# fram_rtc.net
KiCad netlist of a schematic drawn in Altium Designer
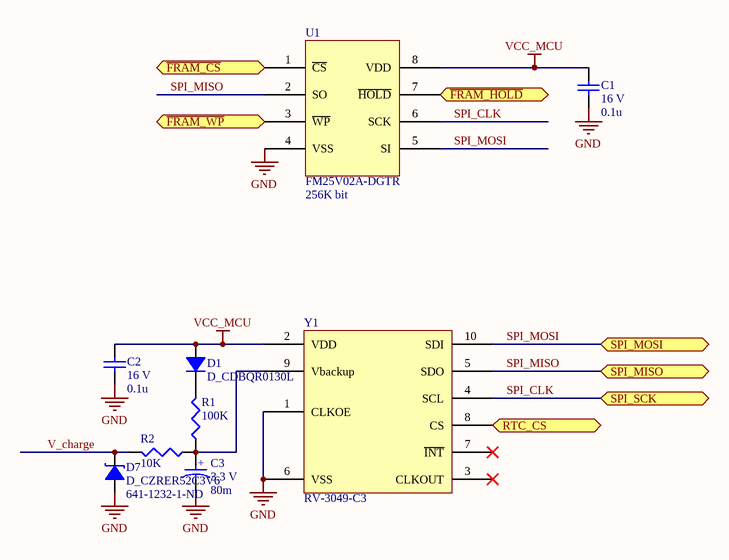
[diagram p0: fram_rtc.SchDoc]

(export (version "E")
  (design (tool "Eeschema 10.0.6"))
  (components
    (comp (ref "C1")
      (value "0.1u")
      (footprint "0402")
      (description "Ceramic capacitor, 0.1u, 16 V, 0402 package")
      (fields
        (field (name "VOLTAGE RATED") "16 V")
        (field (name "TOLERANCE") "10%")
        (field (name "Comment") "Ceramic capacitor")
      )
      (libsource (lib "rlc") (part "C_0.1u_16V_0402_ceramic"))
    )
    (comp (ref "C2")
      (value "0.1u")
      (footprint "0402")
      (description "Ceramic capacitor, 0.1u, 16 V, 0402 package")
      (fields
        (field (name "VOLTAGE RATED") "16 V")
        (field (name "TOLERANCE") "10%")
        (field (name "Comment") "Ceramic capacitor")
      )
      (libsource (lib "rlc") (part "C_0.1u_16V_0402_ceramic"))
    )
    (comp (ref "C3")
      (value "80m")
      (footprint "XH414HG-IV01E")
      (description "Electric double Layer Capacitors")
      (fields
        (field (name "VOLTAGE RATED") "3.3 V")
        (field (name "Comment") "Electric Double Layer Capacitors")
      )
      (libsource (lib "rlc") (part "C_80m_3.3V_supercap"))
    )
    (comp (ref "D1")
      (value "D_CDBQR0130L")
      (footprint "0402 - DIODE")
      (description "SMD Schottky Barrier Diode")
      (libsource (lib "rlc") (part "D_CDBQR0130L"))
    )
    (comp (ref "D7")
      (value "D_CZRER52C3V6")
      (footprint "0503/SOD-723F")
      (description "SURFACE MOUNT ZENER DIODE")
      (fields (field (name "SUPPLIER PART NUMBER 1") "641-1232-1-ND"))
      (libsource (lib "rlc") (part "D_CZRER52C3V6"))
    )
    (comp (ref "R1")
      (value "100K")
      (footprint "0402")
      (description "Chip resistor, 100K, 0402 package")
      (fields (field (name "TOLERANCE") "1%") (field (name "POWER") "1/16 W"))
      (libsource (lib "rlc") (part "R_100K_0402"))
    )
    (comp (ref "R2")
      (value "10K")
      (footprint "0402")
      (description "Chip resistor, 10K, 0402 package")
      (fields (field (name "TOLERANCE") "1%") (field (name "POWER") "1/16 W"))
      (libsource (lib "rlc") (part "R_10K_0402"))
    )
    (comp (ref "U1")
      (value "FM25V02A-DGTR")
      (footprint "TDFN-8")
      (description "256-Kbit (32 K × 8) Serial (SPI) F-RAM")
      (fields (field (name "MANUFACTURER") "Cypress Semiconductor") (field (name "SIZE") "256K bit"))
      (libsource (lib "mem") (part "FM25V02A-DGTR"))
    )
    (comp (ref "Y1")
      (value "RV-3049-C3")
      (footprint "RV-3049-C3")
      (description "Real Time Clock Module with SPI-Bus")
      (libsource (lib "crystal_oscillators_rtc") (part "RV-3049-C3"))
    )
  )
  (nets
    (net (code "1") (name "/RTC_CS") (class "Default")
      (node (ref "Y1") (pin "8") (pinfunction "CS_8") (pintype "passive"))
    )
    (net (code "2") (name "/SPI_CLK") (class "Default")
      (node (ref "U1") (pin "6") (pinfunction "SCK_6") (pintype "passive"))
      (node (ref "Y1") (pin "4") (pinfunction "SCL_4") (pintype "passive"))
    )
    (net (code "3") (name "/SPI_MISO") (class "Default")
      (node (ref "U1") (pin "2") (pinfunction "SO_2") (pintype "passive"))
      (node (ref "Y1") (pin "5") (pinfunction "SDO_5") (pintype "passive"))
    )
    (net (code "4") (name "/SPI_MOSI") (class "Default")
      (node (ref "U1") (pin "5") (pinfunction "SI_5") (pintype "passive"))
      (node (ref "Y1") (pin "10") (pinfunction "SDI_10") (pintype "passive"))
    )
    (net (code "5") (name "/V_charge") (class "Default")
      (node (ref "D7") (pin "2") (pintype "passive"))
      (node (ref "R2") (pin "1") (pintype "passive"))
    )
    (net (code "6") (name "/~{FRAM_CS}") (class "Default")
      (node (ref "U1") (pin "1") (pinfunction "~{CS}_1") (pintype "passive"))
    )
    (net (code "7") (name "/~{FRAM_HOLD}") (class "Default")
      (node (ref "U1") (pin "7") (pinfunction "~{HOLD}_7") (pintype "passive"))
    )
    (net (code "8") (name "/~{FRAM_WP}") (class "Default")
      (node (ref "U1") (pin "3") (pinfunction "~{WP}_3") (pintype "passive"))
    )
    (net (code "9") (name "GND") (class "Default")
      (node (ref "C1") (pin "2") (pintype "passive"))
      (node (ref "C2") (pin "2") (pintype "passive"))
      (node (ref "C3") (pin "2") (pintype "passive"))
      (node (ref "D7") (pin "1") (pintype "passive"))
      (node (ref "U1") (pin "4") (pinfunction "VSS_4") (pintype "passive"))
      (node (ref "Y1") (pin "1") (pinfunction "CLKOE_1") (pintype "passive"))
      (node (ref "Y1") (pin "6") (pinfunction "VSS_6") (pintype "passive"))
    )
    (net (code "10") (name "Net-(D1-Pad2)") (class "Default")
      (node (ref "D1") (pin "2") (pintype "passive"))
      (node (ref "R1") (pin "1") (pintype "passive"))
    )
    (net (code "11") (name "Net-(Y1-Vbackup)") (class "Default")
      (node (ref "C3") (pin "1") (pintype "passive"))
      (node (ref "R1") (pin "2") (pintype "passive"))
      (node (ref "R2") (pin "2") (pintype "passive"))
      (node (ref "Y1") (pin "9") (pinfunction "Vbackup_9") (pintype "passive"))
    )
    (net (code "12") (name "VCC_MCU") (class "Default")
      (node (ref "C1") (pin "1") (pintype "passive"))
      (node (ref "C2") (pin "1") (pintype "passive"))
      (node (ref "D1") (pin "1") (pintype "passive"))
      (node (ref "U1") (pin "8") (pinfunction "VDD_8") (pintype "passive"))
      (node (ref "Y1") (pin "2") (pinfunction "VDD_2") (pintype "passive"))
    )
    (net (code "13") (name "unconnected-(Y1-CLKOUT-Pad3)") (class "Default")
      (node (ref "Y1") (pin "3") (pinfunction "CLKOUT_3") (pintype "passive+no_connect"))
    )
    (net (code "14") (name "unconnected-(Y1-~{INT}-Pad7)") (class "Default")
      (node (ref "Y1") (pin "7") (pinfunction "~{INT}_7") (pintype "passive+no_connect"))
    )
  )
)
